# Sheet2.net
KiCad netlist of a schematic drawn in Altium Designer
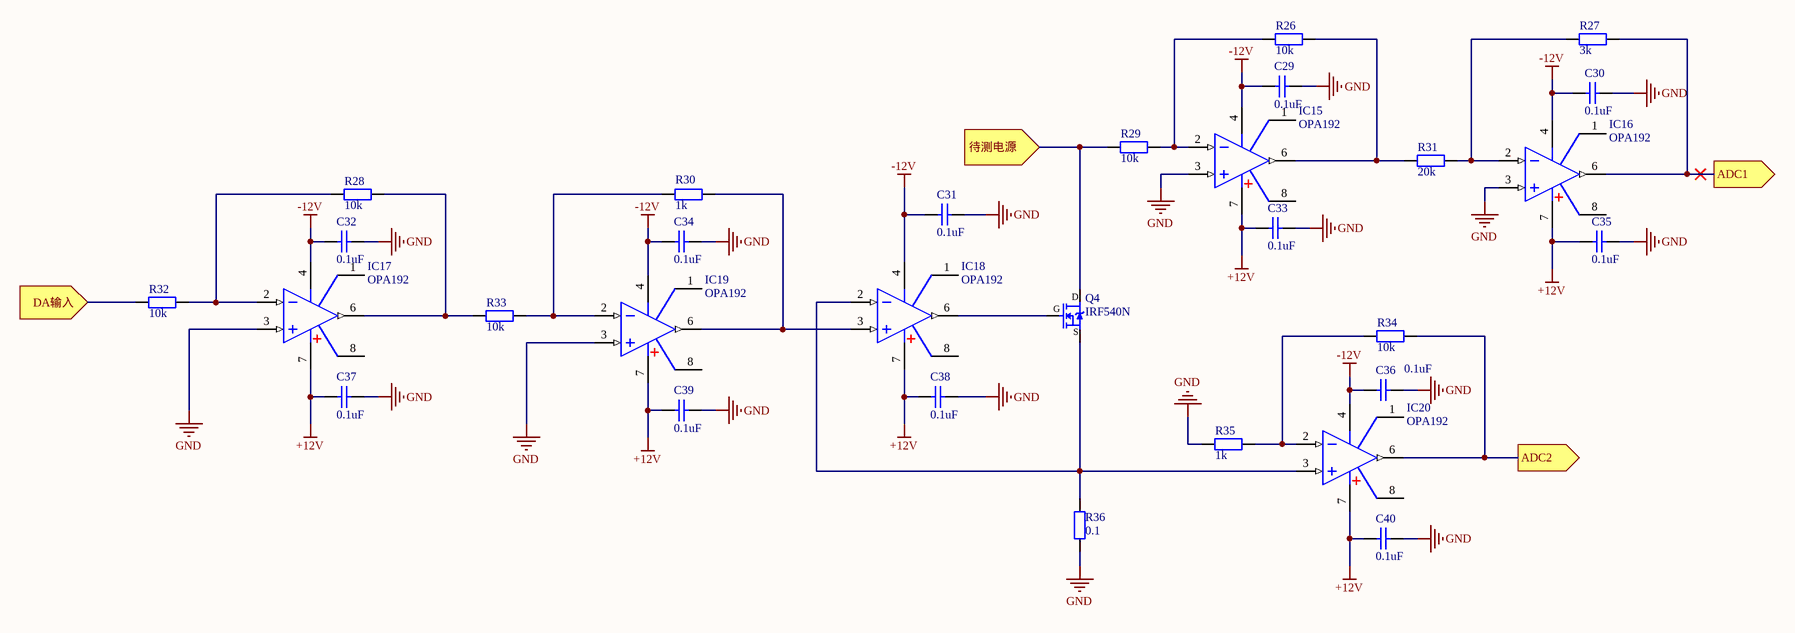
[diagram p0: Sheet2.SchDoc]

(export (version "E")
  (design (tool "Eeschema 10.0.6"))
  (components
    (comp (ref "C29")
      (value "0.1uF")
      (footprint "瓷片电容")
      (description "直插电容")
      (fields (field (name "VOLTAGE") "63V") (field (name "PUBLISHER") "Altium Limited"))
      (libsource (lib "My_Intlib") (part "Cap_DIP"))
    )
    (comp (ref "C30")
      (value "0.1uF")
      (footprint "瓷片电容")
      (description "直插电容")
      (fields (field (name "VOLTAGE") "63V") (field (name "PUBLISHER") "Altium Limited"))
      (libsource (lib "My_Intlib") (part "Cap_DIP"))
    )
    (comp (ref "C31")
      (value "0.1uF")
      (footprint "瓷片电容")
      (description "直插电容")
      (fields (field (name "VOLTAGE") "63V") (field (name "PUBLISHER") "Altium Limited"))
      (libsource (lib "My_Intlib") (part "Cap_DIP"))
    )
    (comp (ref "C32")
      (value "0.1uF")
      (footprint "瓷片电容")
      (description "直插电容")
      (fields (field (name "VOLTAGE") "63V") (field (name "PUBLISHER") "Altium Limited"))
      (libsource (lib "My_Intlib") (part "Cap_DIP"))
    )
    (comp (ref "C33")
      (value "0.1uF")
      (footprint "瓷片电容")
      (description "直插电容")
      (fields (field (name "VOLTAGE") "63V") (field (name "PUBLISHER") "Altium Limited"))
      (libsource (lib "My_Intlib") (part "Cap_DIP"))
    )
    (comp (ref "C34")
      (value "0.1uF")
      (footprint "瓷片电容")
      (description "直插电容")
      (fields (field (name "VOLTAGE") "63V") (field (name "PUBLISHER") "Altium Limited"))
      (libsource (lib "My_Intlib") (part "Cap_DIP"))
    )
    (comp (ref "C35")
      (value "0.1uF")
      (footprint "瓷片电容")
      (description "直插电容")
      (fields (field (name "VOLTAGE") "63V") (field (name "PUBLISHER") "Altium Limited"))
      (libsource (lib "My_Intlib") (part "Cap_DIP"))
    )
    (comp (ref "C36")
      (value "0.1uF")
      (footprint "瓷片电容")
      (description "直插电容")
      (fields (field (name "VOLTAGE") "63V") (field (name "PUBLISHER") "Altium Limited"))
      (libsource (lib "My_Intlib") (part "Cap_DIP"))
    )
    (comp (ref "C37")
      (value "0.1uF")
      (footprint "瓷片电容")
      (description "直插电容")
      (fields (field (name "VOLTAGE") "63V") (field (name "PUBLISHER") "Altium Limited"))
      (libsource (lib "My_Intlib") (part "Cap_DIP"))
    )
    (comp (ref "C38")
      (value "0.1uF")
      (footprint "瓷片电容")
      (description "直插电容")
      (fields (field (name "VOLTAGE") "63V") (field (name "PUBLISHER") "Altium Limited"))
      (libsource (lib "My_Intlib") (part "Cap_DIP"))
    )
    (comp (ref "C39")
      (value "0.1uF")
      (footprint "瓷片电容")
      (description "直插电容")
      (fields (field (name "VOLTAGE") "63V") (field (name "PUBLISHER") "Altium Limited"))
      (libsource (lib "My_Intlib") (part "Cap_DIP"))
    )
    (comp (ref "C40")
      (value "0.1uF")
      (footprint "瓷片电容")
      (description "直插电容")
      (fields (field (name "VOLTAGE") "63V") (field (name "PUBLISHER") "Altium Limited"))
      (libsource (lib "My_Intlib") (part "Cap_DIP"))
    )
    (comp (ref "IC15")
      (value "OPA192")
      (footprint "SOP8_N")
      (description "High-Voltage, Rail-to-Rail Input/Output, 5µV, 0.2µV/˚C, Precision Operational Amplifier")
      (fields (field (name "版权归属") "源创客"))
      (libsource (lib "My_Intlib") (part "OPA192"))
    )
    (comp (ref "IC16")
      (value "OPA192")
      (footprint "SOP8_N")
      (description "High-Voltage, Rail-to-Rail Input/Output, 5µV, 0.2µV/˚C, Precision Operational Amplifier")
      (fields (field (name "版权归属") "源创客"))
      (libsource (lib "My_Intlib") (part "OPA192"))
    )
    (comp (ref "IC17")
      (value "OPA192")
      (footprint "SOP8_N")
      (description "High-Voltage, Rail-to-Rail Input/Output, 5µV, 0.2µV/˚C, Precision Operational Amplifier")
      (fields (field (name "版权归属") "源创客"))
      (libsource (lib "My_Intlib") (part "OPA192"))
    )
    (comp (ref "IC18")
      (value "OPA192")
      (footprint "SOP8_N")
      (description "High-Voltage, Rail-to-Rail Input/Output, 5µV, 0.2µV/˚C, Precision Operational Amplifier")
      (fields (field (name "版权归属") "源创客"))
      (libsource (lib "My_Intlib") (part "OPA192"))
    )
    (comp (ref "IC19")
      (value "OPA192")
      (footprint "SOP8_N")
      (description "High-Voltage, Rail-to-Rail Input/Output, 5µV, 0.2µV/˚C, Precision Operational Amplifier")
      (fields (field (name "版权归属") "源创客"))
      (libsource (lib "My_Intlib") (part "OPA192"))
    )
    (comp (ref "IC20")
      (value "OPA192")
      (footprint "SOP8_N")
      (description "High-Voltage, Rail-to-Rail Input/Output, 5µV, 0.2µV/˚C, Precision Operational Amplifier")
      (fields (field (name "版权归属") "源创客"))
      (libsource (lib "My_Intlib") (part "OPA192"))
    )
    (comp (ref "Q4")
      (value "IRF540N")
      (footprint "TO263-3B")
      (description "N沟场 100V/22A")
      (fields (field (name "版权归属") "源创客"))
      (libsource (lib "My_Intlib") (part "IRF540N"))
    )
    (comp (ref "R26")
      (value "10k")
      (footprint "RS 1/4W")
      (description "直插电阻")
      (libsource (lib "My_Intlib") (part "Res_DIP"))
    )
    (comp (ref "R27")
      (value "3k")
      (footprint "RS 1/4W")
      (description "直插电阻")
      (libsource (lib "My_Intlib") (part "Res_DIP"))
    )
    (comp (ref "R28")
      (value "10k")
      (footprint "RS 1/4W")
      (description "直插电阻")
      (libsource (lib "My_Intlib") (part "Res_DIP"))
    )
    (comp (ref "R29")
      (value "10k")
      (footprint "RS 1/4W")
      (description "直插电阻")
      (libsource (lib "My_Intlib") (part "Res_DIP"))
    )
    (comp (ref "R30")
      (value "1k")
      (footprint "RS 1/4W")
      (description "直插电阻")
      (libsource (lib "My_Intlib") (part "Res_DIP"))
    )
    (comp (ref "R31")
      (value "20k")
      (footprint "RS 1/4W")
      (description "直插电阻")
      (libsource (lib "My_Intlib") (part "Res_DIP"))
    )
    (comp (ref "R32")
      (value "10k")
      (footprint "RS 1/4W")
      (description "直插电阻")
      (libsource (lib "My_Intlib") (part "Res_DIP"))
    )
    (comp (ref "R33")
      (value "10k")
      (footprint "RS 1/4W")
      (description "直插电阻")
      (libsource (lib "My_Intlib") (part "Res_DIP"))
    )
    (comp (ref "R34")
      (value "10k")
      (footprint "RS 1/4W")
      (description "直插电阻")
      (libsource (lib "My_Intlib") (part "Res_DIP"))
    )
    (comp (ref "R35")
      (value "1k")
      (footprint "RS 1/4W")
      (description "直插电阻")
      (libsource (lib "My_Intlib") (part "Res_DIP"))
    )
    (comp (ref "R36")
      (value "0.1")
      (footprint "RS 1/4W")
      (description "直插电阻")
      (libsource (lib "") (part "Res_DIP_1"))
    )
  )
  (nets
    (net (code "1") (name "+12V") (class "Default")
      (node (ref "C33") (pin "1") (pinfunction "1_1") (pintype "passive"))
      (node (ref "C35") (pin "1") (pinfunction "1_1") (pintype "passive"))
      (node (ref "C37") (pin "1") (pinfunction "1_1") (pintype "passive"))
      (node (ref "C38") (pin "1") (pinfunction "1_1") (pintype "passive"))
      (node (ref "C39") (pin "1") (pinfunction "1_1") (pintype "passive"))
      (node (ref "C40") (pin "1") (pinfunction "1_1") (pintype "passive"))
      (node (ref "IC15") (pin "7") (pinfunction "V+_7") (pintype "power_in"))
      (node (ref "IC16") (pin "7") (pinfunction "V+_7") (pintype "power_in"))
      (node (ref "IC17") (pin "7") (pinfunction "V+_7") (pintype "power_in"))
      (node (ref "IC18") (pin "7") (pinfunction "V+_7") (pintype "power_in"))
      (node (ref "IC19") (pin "7") (pinfunction "V+_7") (pintype "power_in"))
      (node (ref "IC20") (pin "7") (pinfunction "V+_7") (pintype "power_in"))
    )
    (net (code "2") (name "-12V") (class "Default")
      (node (ref "C29") (pin "1") (pinfunction "1_1") (pintype "passive"))
      (node (ref "C30") (pin "1") (pinfunction "1_1") (pintype "passive"))
      (node (ref "C31") (pin "1") (pinfunction "1_1") (pintype "passive"))
      (node (ref "C32") (pin "1") (pinfunction "1_1") (pintype "passive"))
      (node (ref "C34") (pin "1") (pinfunction "1_1") (pintype "passive"))
      (node (ref "C36") (pin "1") (pinfunction "1_1") (pintype "passive"))
      (node (ref "IC15") (pin "4") (pinfunction "V-_4") (pintype "power_in"))
      (node (ref "IC16") (pin "4") (pinfunction "V-_4") (pintype "power_in"))
      (node (ref "IC17") (pin "4") (pinfunction "V-_4") (pintype "power_in"))
      (node (ref "IC18") (pin "4") (pinfunction "V-_4") (pintype "power_in"))
      (node (ref "IC19") (pin "4") (pinfunction "V-_4") (pintype "power_in"))
      (node (ref "IC20") (pin "4") (pinfunction "V-_4") (pintype "power_in"))
    )
    (net (code "3") (name "/ADC1") (class "Default")
      (node (ref "IC16") (pin "6") (pinfunction "OUT_6") (pintype "output"))
      (node (ref "R27") (pin "2") (pinfunction "2_2") (pintype "passive"))
    )
    (net (code "4") (name "/ADC2") (class "Default")
      (node (ref "IC20") (pin "6") (pinfunction "OUT_6") (pintype "output"))
      (node (ref "R34") (pin "2") (pinfunction "2_2") (pintype "passive"))
    )
    (net (code "5") (name "/DA输入") (class "Default")
      (node (ref "R32") (pin "1") (pinfunction "1_1") (pintype "passive"))
    )
    (net (code "6") (name "/待测电源") (class "Default")
      (node (ref "Q4") (pin "2") (pinfunction "S_2") (pintype "passive"))
      (node (ref "R29") (pin "1") (pinfunction "1_1") (pintype "passive"))
    )
    (net (code "7") (name "GND") (class "Default")
      (node (ref "C29") (pin "2") (pinfunction "2_2") (pintype "passive"))
      (node (ref "C30") (pin "2") (pinfunction "2_2") (pintype "passive"))
      (node (ref "C31") (pin "2") (pinfunction "2_2") (pintype "passive"))
      (node (ref "C32") (pin "2") (pinfunction "2_2") (pintype "passive"))
      (node (ref "C33") (pin "2") (pinfunction "2_2") (pintype "passive"))
      (node (ref "C34") (pin "2") (pinfunction "2_2") (pintype "passive"))
      (node (ref "C35") (pin "2") (pinfunction "2_2") (pintype "passive"))
      (node (ref "C36") (pin "2") (pinfunction "2_2") (pintype "passive"))
      (node (ref "C37") (pin "2") (pinfunction "2_2") (pintype "passive"))
      (node (ref "C38") (pin "2") (pinfunction "2_2") (pintype "passive"))
      (node (ref "C39") (pin "2") (pinfunction "2_2") (pintype "passive"))
      (node (ref "C40") (pin "2") (pinfunction "2_2") (pintype "passive"))
      (node (ref "IC15") (pin "3") (pinfunction "IN+_3") (pintype "input"))
      (node (ref "IC16") (pin "3") (pinfunction "IN+_3") (pintype "input"))
      (node (ref "IC17") (pin "3") (pinfunction "IN+_3") (pintype "input"))
      (node (ref "IC19") (pin "3") (pinfunction "IN+_3") (pintype "input"))
      (node (ref "R35") (pin "1") (pinfunction "1_1") (pintype "passive"))
      (node (ref "R36") (pin "1") (pinfunction "1_1") (pintype "passive"))
    )
    (net (code "8") (name "Net-(IC15-IN-)") (class "Default")
      (node (ref "IC15") (pin "2") (pinfunction "IN-_2") (pintype "input"))
      (node (ref "R26") (pin "1") (pinfunction "1_1") (pintype "passive"))
      (node (ref "R29") (pin "2") (pinfunction "2_2") (pintype "passive"))
    )
    (net (code "9") (name "Net-(IC15-OUT)") (class "Default")
      (node (ref "IC15") (pin "6") (pinfunction "OUT_6") (pintype "output"))
      (node (ref "R26") (pin "2") (pinfunction "2_2") (pintype "passive"))
      (node (ref "R31") (pin "1") (pinfunction "1_1") (pintype "passive"))
    )
    (net (code "10") (name "Net-(IC16-IN-)") (class "Default")
      (node (ref "IC16") (pin "2") (pinfunction "IN-_2") (pintype "input"))
      (node (ref "R27") (pin "1") (pinfunction "1_1") (pintype "passive"))
      (node (ref "R31") (pin "2") (pinfunction "2_2") (pintype "passive"))
    )
    (net (code "11") (name "Net-(IC17-IN-)") (class "Default")
      (node (ref "IC17") (pin "2") (pinfunction "IN-_2") (pintype "input"))
      (node (ref "R28") (pin "1") (pinfunction "1_1") (pintype "passive"))
      (node (ref "R32") (pin "2") (pinfunction "2_2") (pintype "passive"))
    )
    (net (code "12") (name "Net-(IC17-OUT)") (class "Default")
      (node (ref "IC17") (pin "6") (pinfunction "OUT_6") (pintype "output"))
      (node (ref "R28") (pin "2") (pinfunction "2_2") (pintype "passive"))
      (node (ref "R33") (pin "1") (pinfunction "1_1") (pintype "passive"))
    )
    (net (code "13") (name "Net-(IC18-IN+)") (class "Default")
      (node (ref "IC18") (pin "3") (pinfunction "IN+_3") (pintype "input"))
      (node (ref "IC19") (pin "6") (pinfunction "OUT_6") (pintype "output"))
      (node (ref "R30") (pin "2") (pinfunction "2_2") (pintype "passive"))
    )
    (net (code "14") (name "Net-(IC18-IN-)") (class "Default")
      (node (ref "IC18") (pin "2") (pinfunction "IN-_2") (pintype "input"))
      (node (ref "IC20") (pin "3") (pinfunction "IN+_3") (pintype "input"))
      (node (ref "Q4") (pin "3") (pinfunction "D_3") (pintype "passive"))
      (node (ref "R36") (pin "2") (pinfunction "2_2") (pintype "passive"))
    )
    (net (code "15") (name "Net-(IC18-OUT)") (class "Default")
      (node (ref "IC18") (pin "6") (pinfunction "OUT_6") (pintype "output"))
      (node (ref "Q4") (pin "1") (pinfunction "G_1") (pintype "passive"))
    )
    (net (code "16") (name "Net-(IC19-IN-)") (class "Default")
      (node (ref "IC19") (pin "2") (pinfunction "IN-_2") (pintype "input"))
      (node (ref "R30") (pin "1") (pinfunction "1_1") (pintype "passive"))
      (node (ref "R33") (pin "2") (pinfunction "2_2") (pintype "passive"))
    )
    (net (code "17") (name "Net-(IC20-IN-)") (class "Default")
      (node (ref "IC20") (pin "2") (pinfunction "IN-_2") (pintype "input"))
      (node (ref "R34") (pin "1") (pinfunction "1_1") (pintype "passive"))
      (node (ref "R35") (pin "2") (pinfunction "2_2") (pintype "passive"))
    )
    (net (code "18") (name "unconnected-(IC15-Pad1)") (class "Default")
      (node (ref "IC15") (pin "1") (pinfunction "1_1") (pintype "passive"))
    )
    (net (code "19") (name "unconnected-(IC15-Pad8)") (class "Default")
      (node (ref "IC15") (pin "8") (pinfunction "8_8") (pintype "passive"))
    )
    (net (code "20") (name "unconnected-(IC16-Pad1)") (class "Default")
      (node (ref "IC16") (pin "1") (pinfunction "1_1") (pintype "passive"))
    )
    (net (code "21") (name "unconnected-(IC16-Pad8)") (class "Default")
      (node (ref "IC16") (pin "8") (pinfunction "8_8") (pintype "passive"))
    )
    (net (code "22") (name "unconnected-(IC17-Pad1)") (class "Default")
      (node (ref "IC17") (pin "1") (pinfunction "1_1") (pintype "passive"))
    )
    (net (code "23") (name "unconnected-(IC17-Pad8)") (class "Default")
      (node (ref "IC17") (pin "8") (pinfunction "8_8") (pintype "passive"))
    )
    (net (code "24") (name "unconnected-(IC18-Pad1)") (class "Default")
      (node (ref "IC18") (pin "1") (pinfunction "1_1") (pintype "passive"))
    )
    (net (code "25") (name "unconnected-(IC18-Pad8)") (class "Default")
      (node (ref "IC18") (pin "8") (pinfunction "8_8") (pintype "passive"))
    )
    (net (code "26") (name "unconnected-(IC19-Pad1)") (class "Default")
      (node (ref "IC19") (pin "1") (pinfunction "1_1") (pintype "passive"))
    )
    (net (code "27") (name "unconnected-(IC19-Pad8)") (class "Default")
      (node (ref "IC19") (pin "8") (pinfunction "8_8") (pintype "passive"))
    )
    (net (code "28") (name "unconnected-(IC20-Pad1)") (class "Default")
      (node (ref "IC20") (pin "1") (pinfunction "1_1") (pintype "passive"))
    )
    (net (code "29") (name "unconnected-(IC20-Pad8)") (class "Default")
      (node (ref "IC20") (pin "8") (pinfunction "8_8") (pintype "passive"))
    )
  )
)
